# tivac-shield-power-board.net
KiCad netlist of a schematic drawn in EAGLE
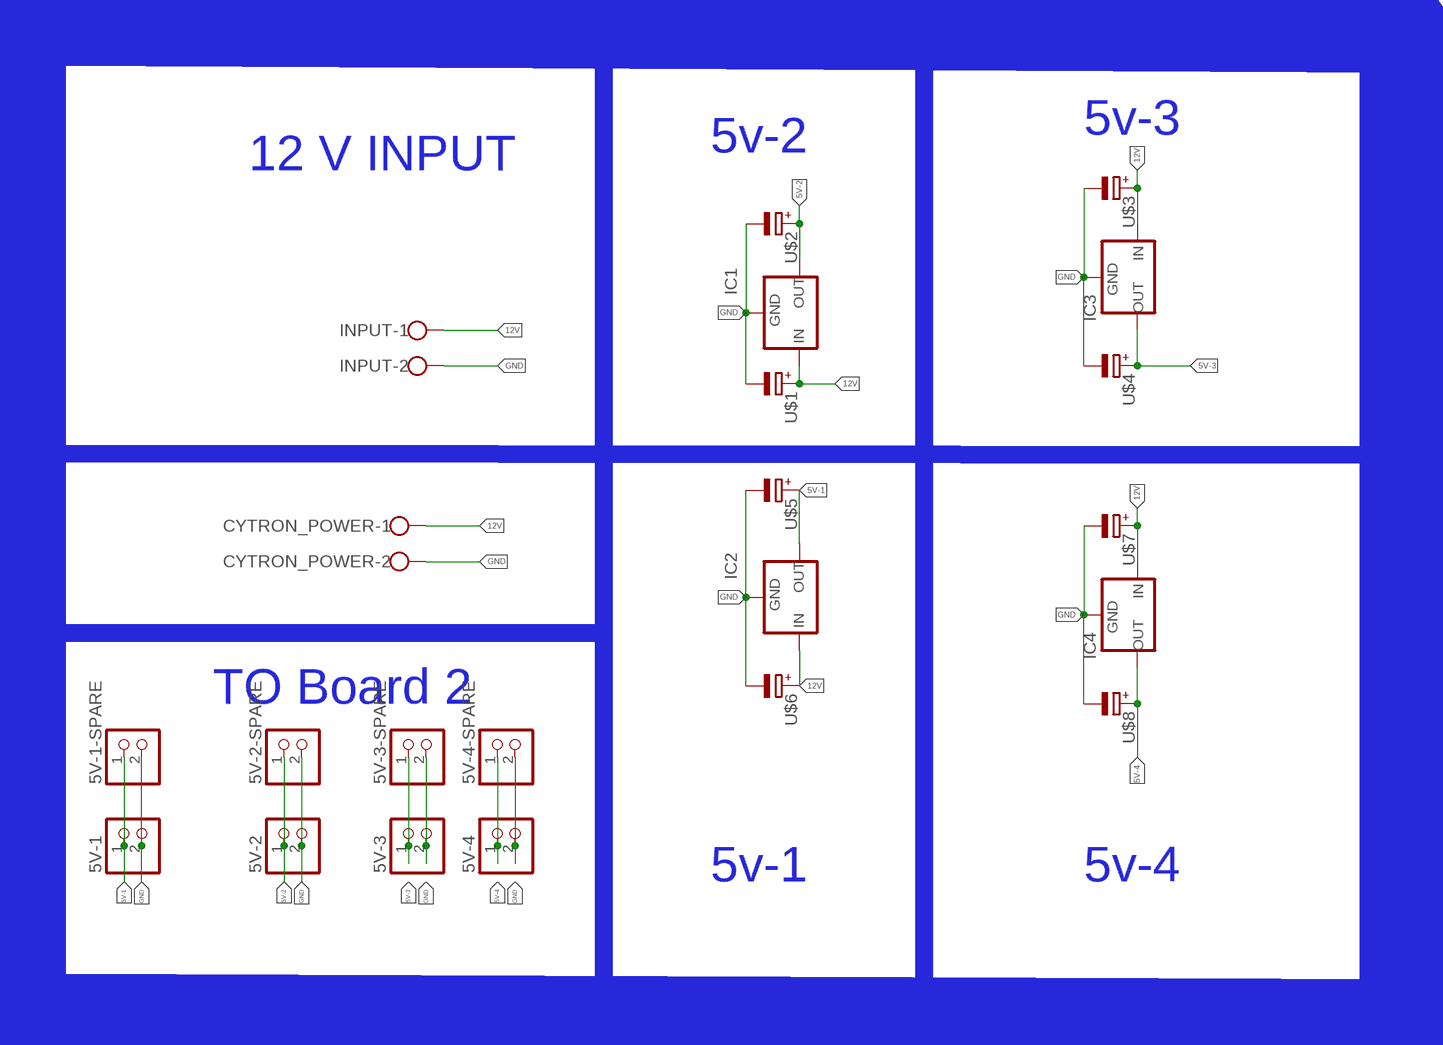
[diagram p0: schematic, sheet 1]

(export (version "E")
  (design (tool "Eeschema 10.0.6"))
  (components
    (comp (ref "5V-1")
      (value "PINHD-1X2")
      (footprint "eagle-import:1X02")
      (libsource (lib "eagle-import") (part "PINHD-1X2"))
    )
    (comp (ref "5V-1-SPARE")
      (value "PINHD-1X2")
      (footprint "eagle-import:1X02")
      (libsource (lib "eagle-import") (part "PINHD-1X2"))
    )
    (comp (ref "5V-2")
      (value "PINHD-1X2")
      (footprint "eagle-import:1X02")
      (libsource (lib "eagle-import") (part "PINHD-1X2"))
    )
    (comp (ref "5V-2-SPARE")
      (value "PINHD-1X2")
      (footprint "eagle-import:1X02")
      (libsource (lib "eagle-import") (part "PINHD-1X2"))
    )
    (comp (ref "5V-3")
      (value "PINHD-1X2")
      (footprint "eagle-import:1X02")
      (libsource (lib "eagle-import") (part "PINHD-1X2"))
    )
    (comp (ref "5V-3-SPARE")
      (value "PINHD-1X2")
      (footprint "eagle-import:1X02")
      (libsource (lib "eagle-import") (part "PINHD-1X2"))
    )
    (comp (ref "5V-4")
      (value "PINHD-1X2")
      (footprint "eagle-import:1X02")
      (libsource (lib "eagle-import") (part "PINHD-1X2"))
    )
    (comp (ref "5V-4-SPARE")
      (value "PINHD-1X2")
      (footprint "eagle-import:1X02")
      (libsource (lib "eagle-import") (part "PINHD-1X2"))
    )
    (comp (ref "CYTRON_POWER")
      (value "W237-113")
      (footprint "eagle-import:W237-113")
      (libsource (lib "eagle-import") (part "W237-113"))
    )
    (comp (ref "IC1")
      (value "78XX-METAL")
      (footprint "eagle-import:TO3-79")
      (libsource (lib "eagle-import") (part "78XX-METAL"))
    )
    (comp (ref "IC2")
      (value "78XX-METAL")
      (footprint "eagle-import:TO3-79")
      (libsource (lib "eagle-import") (part "78XX-METAL"))
    )
    (comp (ref "IC3")
      (value "78XXS")
      (footprint "eagle-import:78XXS")
      (libsource (lib "eagle-import") (part "78XXS"))
    )
    (comp (ref "IC4")
      (value "78XXS")
      (footprint "eagle-import:78XXS")
      (libsource (lib "eagle-import") (part "78XXS"))
    )
    (comp (ref "INPUT")
      (value "W237-113")
      (footprint "eagle-import:W237-113")
      (libsource (lib "eagle-import") (part "W237-113"))
    )
    (comp (ref "U$1")
      (value "CAP_POL")
      (footprint "eagle-import:E3,5-8")
      (libsource (lib "eagle-import") (part "CAP_POL"))
    )
    (comp (ref "U$2")
      (value "CAP_POL")
      (footprint "eagle-import:E3,5-8")
      (libsource (lib "eagle-import") (part "CAP_POL"))
    )
    (comp (ref "U$3")
      (value "CAP_POL")
      (footprint "eagle-import:E3,5-8")
      (libsource (lib "eagle-import") (part "CAP_POL"))
    )
    (comp (ref "U$4")
      (value "CAP_POL")
      (footprint "eagle-import:E3,5-8")
      (libsource (lib "eagle-import") (part "CAP_POL"))
    )
    (comp (ref "U$5")
      (value "CAP_POL")
      (footprint "eagle-import:E3,5-8")
      (libsource (lib "eagle-import") (part "CAP_POL"))
    )
    (comp (ref "U$6")
      (value "CAP_POL")
      (footprint "eagle-import:E3,5-8")
      (libsource (lib "eagle-import") (part "CAP_POL"))
    )
    (comp (ref "U$7")
      (value "CAP_POL")
      (footprint "eagle-import:E3,5-8")
      (libsource (lib "eagle-import") (part "CAP_POL"))
    )
    (comp (ref "U$8")
      (value "CAP_POL")
      (footprint "eagle-import:E3,5-8")
      (libsource (lib "eagle-import") (part "CAP_POL"))
    )
  )
  (nets
    (net (code "1") (name "5V-1") (class "Default")
      (node (ref "5V-1") (pin "1") (pinfunction "1_1") (pintype "passive"))
      (node (ref "5V-1-SPARE") (pin "1") (pinfunction "1_1") (pintype "passive"))
      (node (ref "IC2") (pin "1") (pinfunction "OUT_1") (pintype "passive"))
      (node (ref "U$5") (pin "+") (pinfunction "+_+") (pintype "passive"))
    )
    (net (code "2") (name "5V-2") (class "Default")
      (node (ref "5V-2") (pin "1") (pinfunction "1_1") (pintype "passive"))
      (node (ref "5V-2-SPARE") (pin "1") (pinfunction "1_1") (pintype "passive"))
      (node (ref "IC1") (pin "1") (pinfunction "OUT_1") (pintype "passive"))
      (node (ref "U$2") (pin "+") (pinfunction "+_+") (pintype "passive"))
    )
    (net (code "3") (name "5V-3") (class "Default")
      (node (ref "5V-3") (pin "1") (pinfunction "1_1") (pintype "passive"))
      (node (ref "5V-3-SPARE") (pin "1") (pinfunction "1_1") (pintype "passive"))
      (node (ref "IC3") (pin "OUT") (pinfunction "OUT_OUT") (pintype "passive"))
      (node (ref "U$4") (pin "+") (pinfunction "+_+") (pintype "passive"))
    )
    (net (code "4") (name "5V-4") (class "Default")
      (node (ref "5V-4") (pin "1") (pinfunction "1_1") (pintype "passive"))
      (node (ref "5V-4-SPARE") (pin "1") (pinfunction "1_1") (pintype "passive"))
      (node (ref "IC4") (pin "OUT") (pinfunction "OUT_OUT") (pintype "passive"))
      (node (ref "U$8") (pin "+") (pinfunction "+_+") (pintype "passive"))
    )
    (net (code "5") (name "12V") (class "Default")
      (node (ref "CYTRON_POWER") (pin "1") (pinfunction "KL_1") (pintype "passive"))
      (node (ref "IC1") (pin "3") (pinfunction "IN_3") (pintype "input"))
      (node (ref "IC2") (pin "3") (pinfunction "IN_3") (pintype "input"))
      (node (ref "IC3") (pin "IN") (pinfunction "IN_IN") (pintype "input"))
      (node (ref "IC4") (pin "IN") (pinfunction "IN_IN") (pintype "input"))
      (node (ref "INPUT") (pin "1") (pinfunction "KL_1") (pintype "passive"))
      (node (ref "U$1") (pin "+") (pinfunction "+_+") (pintype "passive"))
      (node (ref "U$3") (pin "+") (pinfunction "+_+") (pintype "passive"))
      (node (ref "U$6") (pin "+") (pinfunction "+_+") (pintype "passive"))
      (node (ref "U$7") (pin "+") (pinfunction "+_+") (pintype "passive"))
    )
    (net (code "6") (name "GND") (class "Default")
      (node (ref "5V-1") (pin "2") (pinfunction "2_2") (pintype "passive"))
      (node (ref "5V-1-SPARE") (pin "2") (pinfunction "2_2") (pintype "passive"))
      (node (ref "5V-2") (pin "2") (pinfunction "2_2") (pintype "passive"))
      (node (ref "5V-2-SPARE") (pin "2") (pinfunction "2_2") (pintype "passive"))
      (node (ref "5V-3") (pin "2") (pinfunction "2_2") (pintype "passive"))
      (node (ref "5V-3-SPARE") (pin "2") (pinfunction "2_2") (pintype "passive"))
      (node (ref "5V-4") (pin "2") (pinfunction "2_2") (pintype "passive"))
      (node (ref "5V-4-SPARE") (pin "2") (pinfunction "2_2") (pintype "passive"))
      (node (ref "CYTRON_POWER") (pin "2") (pinfunction "KL_2") (pintype "passive"))
      (node (ref "IC1") (pin "2") (pinfunction "GND_2") (pintype "input"))
      (node (ref "IC2") (pin "2") (pinfunction "GND_2") (pintype "input"))
      (node (ref "IC3") (pin "GND") (pinfunction "GND_GND") (pintype "input"))
      (node (ref "IC4") (pin "GND") (pinfunction "GND_GND") (pintype "input"))
      (node (ref "INPUT") (pin "2") (pinfunction "KL_2") (pintype "passive"))
      (node (ref "U$1") (pin "-") (pinfunction "-_-") (pintype "passive"))
      (node (ref "U$2") (pin "-") (pinfunction "-_-") (pintype "passive"))
      (node (ref "U$3") (pin "-") (pinfunction "-_-") (pintype "passive"))
      (node (ref "U$4") (pin "-") (pinfunction "-_-") (pintype "passive"))
      (node (ref "U$5") (pin "-") (pinfunction "-_-") (pintype "passive"))
      (node (ref "U$6") (pin "-") (pinfunction "-_-") (pintype "passive"))
      (node (ref "U$7") (pin "-") (pinfunction "-_-") (pintype "passive"))
      (node (ref "U$8") (pin "-") (pinfunction "-_-") (pintype "passive"))
    )
  )
)
